# SideXSolarPanel.net
KiCad netlist of a schematic drawn in EAGLE
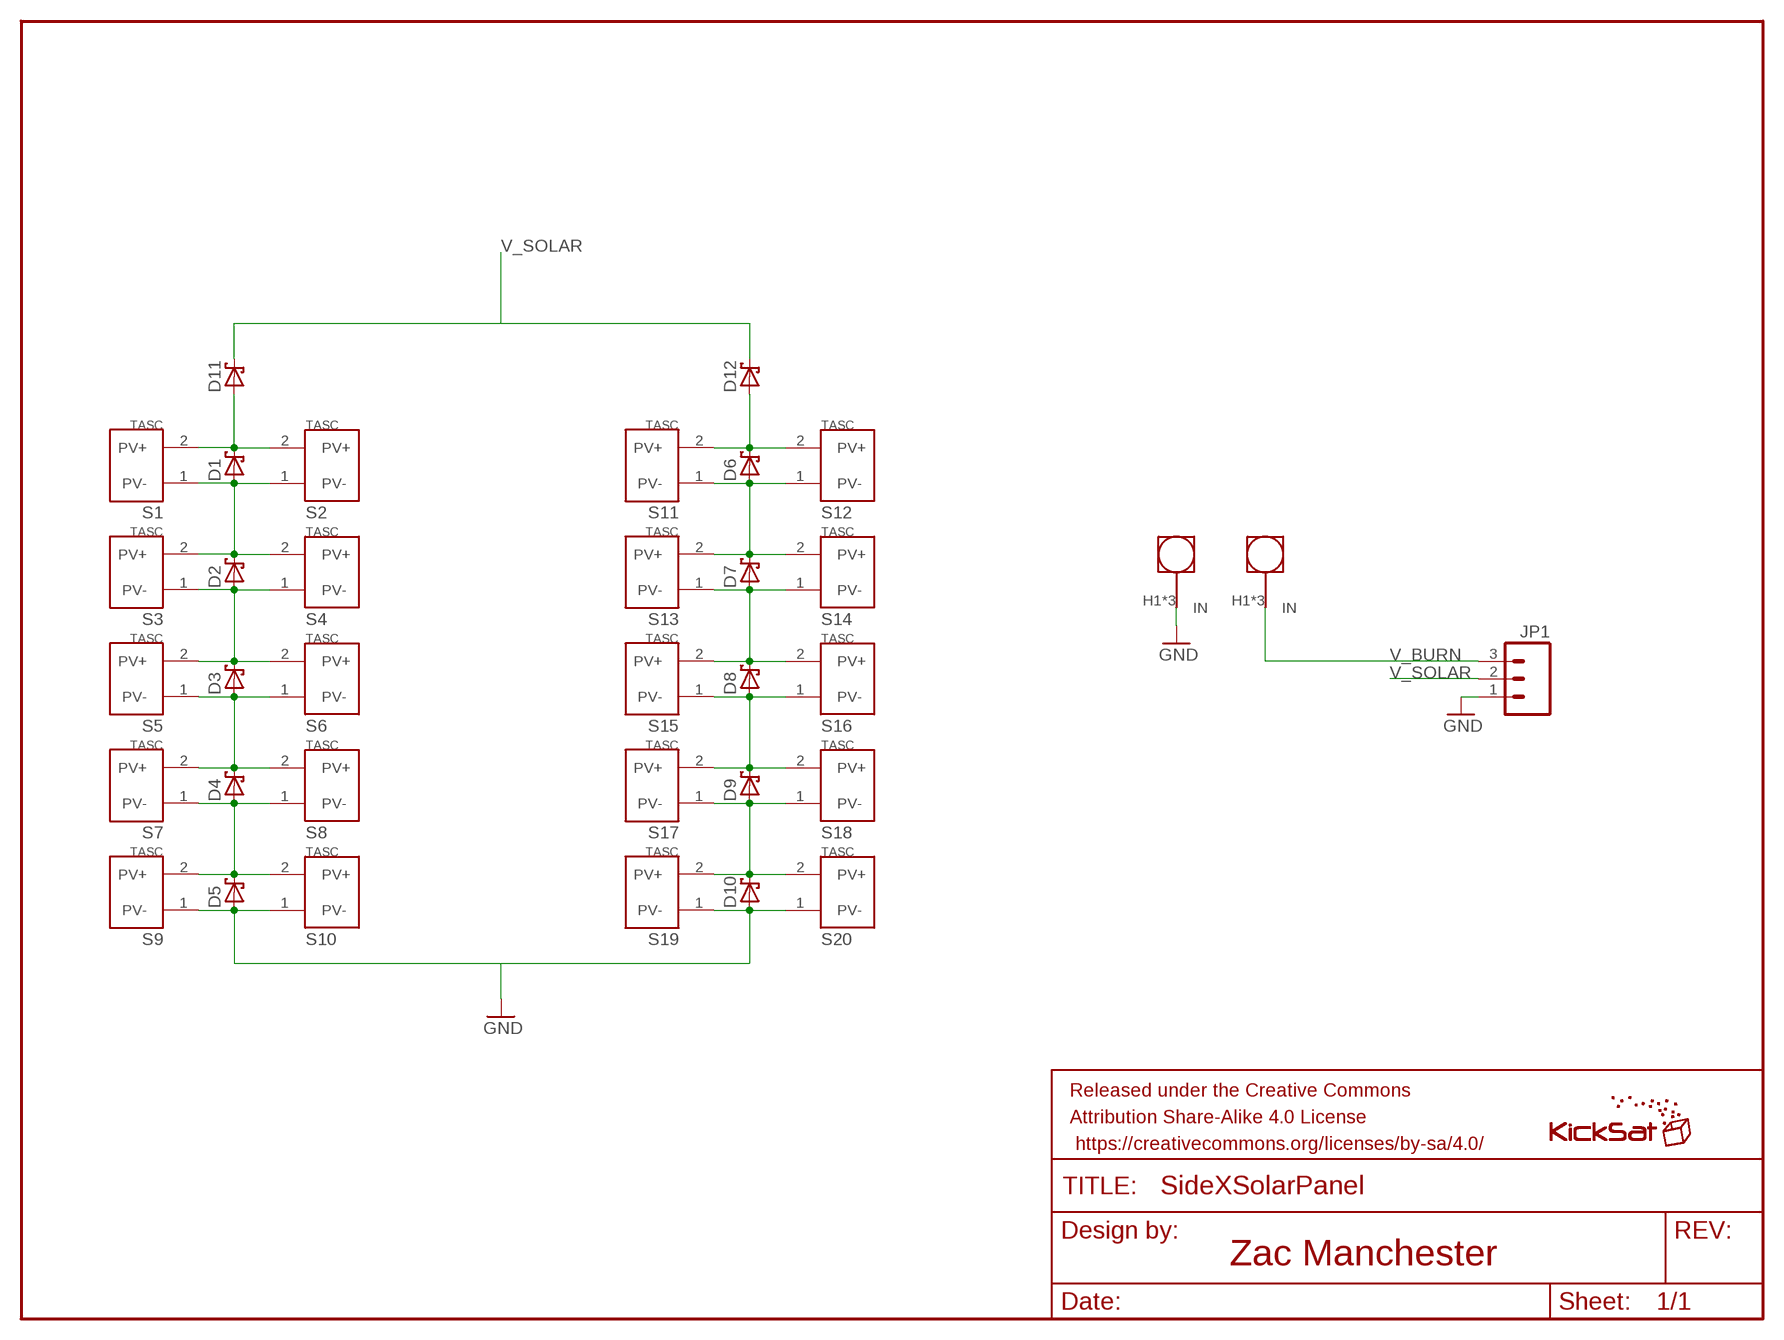
[diagram p0: schematic, sheet 1]

(export (version "E")
  (design (tool "Eeschema 10.0.6"))
  (components
    (comp (ref "D1")
      (value "SB_DIODE")
      (footprint "eagle-import:SB_DIODE")
      (libsource (lib "eagle-import") (part "SB_DIODE"))
    )
    (comp (ref "D2")
      (value "SB_DIODE")
      (footprint "eagle-import:SB_DIODE")
      (libsource (lib "eagle-import") (part "SB_DIODE"))
    )
    (comp (ref "D3")
      (value "SB_DIODE")
      (footprint "eagle-import:SB_DIODE")
      (libsource (lib "eagle-import") (part "SB_DIODE"))
    )
    (comp (ref "D4")
      (value "SB_DIODE")
      (footprint "eagle-import:SB_DIODE")
      (libsource (lib "eagle-import") (part "SB_DIODE"))
    )
    (comp (ref "D5")
      (value "SB_DIODE")
      (footprint "eagle-import:SB_DIODE")
      (libsource (lib "eagle-import") (part "SB_DIODE"))
    )
    (comp (ref "D6")
      (value "SB_DIODE")
      (footprint "eagle-import:SB_DIODE")
      (libsource (lib "eagle-import") (part "SB_DIODE"))
    )
    (comp (ref "D7")
      (value "SB_DIODE")
      (footprint "eagle-import:SB_DIODE")
      (libsource (lib "eagle-import") (part "SB_DIODE"))
    )
    (comp (ref "D8")
      (value "SB_DIODE")
      (footprint "eagle-import:SB_DIODE")
      (libsource (lib "eagle-import") (part "SB_DIODE"))
    )
    (comp (ref "D9")
      (value "SB_DIODE")
      (footprint "eagle-import:SB_DIODE")
      (libsource (lib "eagle-import") (part "SB_DIODE"))
    )
    (comp (ref "D10")
      (value "SB_DIODE")
      (footprint "eagle-import:SB_DIODE")
      (libsource (lib "eagle-import") (part "SB_DIODE"))
    )
    (comp (ref "D11")
      (value "SB_DIODE")
      (footprint "eagle-import:SB_DIODE")
      (libsource (lib "eagle-import") (part "SB_DIODE"))
    )
    (comp (ref "D12")
      (value "SB_DIODE")
      (footprint "eagle-import:SB_DIODE")
      (libsource (lib "eagle-import") (part "SB_DIODE"))
    )
    (comp (ref "FRAME1")
      (value "FRAME-LETTER")
      (footprint "eagle-import:CREATIVE_COMMONS")
      (libsource (lib "eagle-import") (part "FRAME-LETTER"))
    )
    (comp (ref "JP1")
      (value "M03POLAR_LOCK")
      (footprint "eagle-import:MOLEX-1X3_LOCK")
      (libsource (lib "eagle-import") (part "M03POLAR_LOCK"))
    )
    (comp (ref "S1")
      (value "SOLAR_CELL")
      (footprint "eagle-import:SOLAR_CELL")
      (libsource (lib "eagle-import") (part "SOLAR_CELL"))
    )
    (comp (ref "S2")
      (value "SOLAR_CELL")
      (footprint "eagle-import:SOLAR_CELL")
      (libsource (lib "eagle-import") (part "SOLAR_CELL"))
    )
    (comp (ref "S3")
      (value "SOLAR_CELL")
      (footprint "eagle-import:SOLAR_CELL")
      (libsource (lib "eagle-import") (part "SOLAR_CELL"))
    )
    (comp (ref "S4")
      (value "SOLAR_CELL")
      (footprint "eagle-import:SOLAR_CELL")
      (libsource (lib "eagle-import") (part "SOLAR_CELL"))
    )
    (comp (ref "S5")
      (value "SOLAR_CELL")
      (footprint "eagle-import:SOLAR_CELL")
      (libsource (lib "eagle-import") (part "SOLAR_CELL"))
    )
    (comp (ref "S6")
      (value "SOLAR_CELL")
      (footprint "eagle-import:SOLAR_CELL")
      (libsource (lib "eagle-import") (part "SOLAR_CELL"))
    )
    (comp (ref "S7")
      (value "SOLAR_CELL")
      (footprint "eagle-import:SOLAR_CELL")
      (libsource (lib "eagle-import") (part "SOLAR_CELL"))
    )
    (comp (ref "S8")
      (value "SOLAR_CELL")
      (footprint "eagle-import:SOLAR_CELL")
      (libsource (lib "eagle-import") (part "SOLAR_CELL"))
    )
    (comp (ref "S9")
      (value "SOLAR_CELL")
      (footprint "eagle-import:SOLAR_CELL")
      (libsource (lib "eagle-import") (part "SOLAR_CELL"))
    )
    (comp (ref "S10")
      (value "SOLAR_CELL")
      (footprint "eagle-import:SOLAR_CELL")
      (libsource (lib "eagle-import") (part "SOLAR_CELL"))
    )
    (comp (ref "S11")
      (value "SOLAR_CELL")
      (footprint "eagle-import:SOLAR_CELL")
      (libsource (lib "eagle-import") (part "SOLAR_CELL"))
    )
    (comp (ref "S12")
      (value "SOLAR_CELL")
      (footprint "eagle-import:SOLAR_CELL")
      (libsource (lib "eagle-import") (part "SOLAR_CELL"))
    )
    (comp (ref "S13")
      (value "SOLAR_CELL")
      (footprint "eagle-import:SOLAR_CELL")
      (libsource (lib "eagle-import") (part "SOLAR_CELL"))
    )
    (comp (ref "S14")
      (value "SOLAR_CELL")
      (footprint "eagle-import:SOLAR_CELL")
      (libsource (lib "eagle-import") (part "SOLAR_CELL"))
    )
    (comp (ref "S15")
      (value "SOLAR_CELL")
      (footprint "eagle-import:SOLAR_CELL")
      (libsource (lib "eagle-import") (part "SOLAR_CELL"))
    )
    (comp (ref "S16")
      (value "SOLAR_CELL")
      (footprint "eagle-import:SOLAR_CELL")
      (libsource (lib "eagle-import") (part "SOLAR_CELL"))
    )
    (comp (ref "S17")
      (value "SOLAR_CELL")
      (footprint "eagle-import:SOLAR_CELL")
      (libsource (lib "eagle-import") (part "SOLAR_CELL"))
    )
    (comp (ref "S18")
      (value "SOLAR_CELL")
      (footprint "eagle-import:SOLAR_CELL")
      (libsource (lib "eagle-import") (part "SOLAR_CELL"))
    )
    (comp (ref "S19")
      (value "SOLAR_CELL")
      (footprint "eagle-import:SOLAR_CELL")
      (libsource (lib "eagle-import") (part "SOLAR_CELL"))
    )
    (comp (ref "S20")
      (value "SOLAR_CELL")
      (footprint "eagle-import:SOLAR_CELL")
      (libsource (lib "eagle-import") (part "SOLAR_CELL"))
    )
    (comp (ref "U$1")
      (value "BURNER")
      (footprint "eagle-import:BURNER")
      (libsource (lib "eagle-import") (part "BURNER"))
    )
    (comp (ref "U$2")
      (value "BURNER")
      (footprint "eagle-import:BURNER")
      (libsource (lib "eagle-import") (part "BURNER"))
    )
    (comp (ref "U$3")
      (value "KICKSAT_LOGO")
      (footprint "eagle-import:KICKSAT_LOGO")
      (libsource (lib "eagle-import") (part "KICKSAT_LOGO"))
    )
  )
  (nets
    (net (code "1") (name "/V_BURN") (class "Default")
      (node (ref "JP1") (pin "3") (pinfunction "3_3") (pintype "passive"))
      (node (ref "U$1") (pin "H1") (pinfunction "IN_H1") (pintype "bidirectional"))
      (node (ref "U$1") (pin "H2") (pinfunction "IN_H2") (pintype "bidirectional"))
      (node (ref "U$1") (pin "H3") (pinfunction "IN_H3") (pintype "bidirectional"))
    )
    (net (code "2") (name "/V_SOLAR") (class "Default")
      (node (ref "D11") (pin "NEG") (pinfunction "NEG_NEG") (pintype "passive"))
      (node (ref "D12") (pin "NEG") (pinfunction "NEG_NEG") (pintype "passive"))
      (node (ref "JP1") (pin "2") (pinfunction "2_2") (pintype "passive"))
    )
    (net (code "3") (name "GND") (class "Default")
      (node (ref "D10") (pin "POS") (pinfunction "POS_POS") (pintype "passive"))
      (node (ref "D5") (pin "POS") (pinfunction "POS_POS") (pintype "passive"))
      (node (ref "JP1") (pin "1") (pinfunction "1_1") (pintype "passive"))
      (node (ref "S10") (pin "1") (pinfunction "PV-_1") (pintype "bidirectional"))
      (node (ref "S19") (pin "1") (pinfunction "PV-_1") (pintype "bidirectional"))
      (node (ref "S20") (pin "1") (pinfunction "PV-_1") (pintype "bidirectional"))
      (node (ref "S9") (pin "1") (pinfunction "PV-_1") (pintype "bidirectional"))
      (node (ref "U$2") (pin "H1") (pinfunction "IN_H1") (pintype "bidirectional"))
      (node (ref "U$2") (pin "H2") (pinfunction "IN_H2") (pintype "bidirectional"))
      (node (ref "U$2") (pin "H3") (pinfunction "IN_H3") (pintype "bidirectional"))
    )
    (net (code "4") (name "Net-(S1-PV+)") (class "Default")
      (node (ref "D1") (pin "NEG") (pinfunction "NEG_NEG") (pintype "passive"))
      (node (ref "D11") (pin "POS") (pinfunction "POS_POS") (pintype "passive"))
      (node (ref "S1") (pin "2") (pinfunction "PV+_2") (pintype "bidirectional"))
      (node (ref "S2") (pin "2") (pinfunction "PV+_2") (pintype "bidirectional"))
    )
    (net (code "5") (name "Net-(S1-PV-)") (class "Default")
      (node (ref "D1") (pin "POS") (pinfunction "POS_POS") (pintype "passive"))
      (node (ref "D2") (pin "NEG") (pinfunction "NEG_NEG") (pintype "passive"))
      (node (ref "S1") (pin "1") (pinfunction "PV-_1") (pintype "bidirectional"))
      (node (ref "S2") (pin "1") (pinfunction "PV-_1") (pintype "bidirectional"))
      (node (ref "S3") (pin "2") (pinfunction "PV+_2") (pintype "bidirectional"))
      (node (ref "S4") (pin "2") (pinfunction "PV+_2") (pintype "bidirectional"))
    )
    (net (code "6") (name "Net-(S3-PV-)") (class "Default")
      (node (ref "D2") (pin "POS") (pinfunction "POS_POS") (pintype "passive"))
      (node (ref "D3") (pin "NEG") (pinfunction "NEG_NEG") (pintype "passive"))
      (node (ref "S3") (pin "1") (pinfunction "PV-_1") (pintype "bidirectional"))
      (node (ref "S4") (pin "1") (pinfunction "PV-_1") (pintype "bidirectional"))
      (node (ref "S5") (pin "2") (pinfunction "PV+_2") (pintype "bidirectional"))
      (node (ref "S6") (pin "2") (pinfunction "PV+_2") (pintype "bidirectional"))
    )
    (net (code "7") (name "Net-(S5-PV-)") (class "Default")
      (node (ref "D3") (pin "POS") (pinfunction "POS_POS") (pintype "passive"))
      (node (ref "D4") (pin "NEG") (pinfunction "NEG_NEG") (pintype "passive"))
      (node (ref "S5") (pin "1") (pinfunction "PV-_1") (pintype "bidirectional"))
      (node (ref "S6") (pin "1") (pinfunction "PV-_1") (pintype "bidirectional"))
      (node (ref "S7") (pin "2") (pinfunction "PV+_2") (pintype "bidirectional"))
      (node (ref "S8") (pin "2") (pinfunction "PV+_2") (pintype "bidirectional"))
    )
    (net (code "8") (name "Net-(S10-PV+)") (class "Default")
      (node (ref "D4") (pin "POS") (pinfunction "POS_POS") (pintype "passive"))
      (node (ref "D5") (pin "NEG") (pinfunction "NEG_NEG") (pintype "passive"))
      (node (ref "S10") (pin "2") (pinfunction "PV+_2") (pintype "bidirectional"))
      (node (ref "S7") (pin "1") (pinfunction "PV-_1") (pintype "bidirectional"))
      (node (ref "S8") (pin "1") (pinfunction "PV-_1") (pintype "bidirectional"))
      (node (ref "S9") (pin "2") (pinfunction "PV+_2") (pintype "bidirectional"))
    )
    (net (code "9") (name "Net-(S11-PV+)") (class "Default")
      (node (ref "D12") (pin "POS") (pinfunction "POS_POS") (pintype "passive"))
      (node (ref "D6") (pin "NEG") (pinfunction "NEG_NEG") (pintype "passive"))
      (node (ref "S11") (pin "2") (pinfunction "PV+_2") (pintype "bidirectional"))
      (node (ref "S12") (pin "2") (pinfunction "PV+_2") (pintype "bidirectional"))
    )
    (net (code "10") (name "Net-(S11-PV-)") (class "Default")
      (node (ref "D6") (pin "POS") (pinfunction "POS_POS") (pintype "passive"))
      (node (ref "D7") (pin "NEG") (pinfunction "NEG_NEG") (pintype "passive"))
      (node (ref "S11") (pin "1") (pinfunction "PV-_1") (pintype "bidirectional"))
      (node (ref "S12") (pin "1") (pinfunction "PV-_1") (pintype "bidirectional"))
      (node (ref "S13") (pin "2") (pinfunction "PV+_2") (pintype "bidirectional"))
      (node (ref "S14") (pin "2") (pinfunction "PV+_2") (pintype "bidirectional"))
    )
    (net (code "11") (name "Net-(S13-PV-)") (class "Default")
      (node (ref "D7") (pin "POS") (pinfunction "POS_POS") (pintype "passive"))
      (node (ref "D8") (pin "NEG") (pinfunction "NEG_NEG") (pintype "passive"))
      (node (ref "S13") (pin "1") (pinfunction "PV-_1") (pintype "bidirectional"))
      (node (ref "S14") (pin "1") (pinfunction "PV-_1") (pintype "bidirectional"))
      (node (ref "S15") (pin "2") (pinfunction "PV+_2") (pintype "bidirectional"))
      (node (ref "S16") (pin "2") (pinfunction "PV+_2") (pintype "bidirectional"))
    )
    (net (code "12") (name "Net-(S15-PV-)") (class "Default")
      (node (ref "D8") (pin "POS") (pinfunction "POS_POS") (pintype "passive"))
      (node (ref "D9") (pin "NEG") (pinfunction "NEG_NEG") (pintype "passive"))
      (node (ref "S15") (pin "1") (pinfunction "PV-_1") (pintype "bidirectional"))
      (node (ref "S16") (pin "1") (pinfunction "PV-_1") (pintype "bidirectional"))
      (node (ref "S17") (pin "2") (pinfunction "PV+_2") (pintype "bidirectional"))
      (node (ref "S18") (pin "2") (pinfunction "PV+_2") (pintype "bidirectional"))
    )
    (net (code "13") (name "Net-(S17-PV-)") (class "Default")
      (node (ref "D10") (pin "NEG") (pinfunction "NEG_NEG") (pintype "passive"))
      (node (ref "D9") (pin "POS") (pinfunction "POS_POS") (pintype "passive"))
      (node (ref "S17") (pin "1") (pinfunction "PV-_1") (pintype "bidirectional"))
      (node (ref "S18") (pin "1") (pinfunction "PV-_1") (pintype "bidirectional"))
      (node (ref "S19") (pin "2") (pinfunction "PV+_2") (pintype "bidirectional"))
      (node (ref "S20") (pin "2") (pinfunction "PV+_2") (pintype "bidirectional"))
    )
  )
)
